# LM3670_3_3.net
KiCad netlist of a schematic drawn in EAGLE
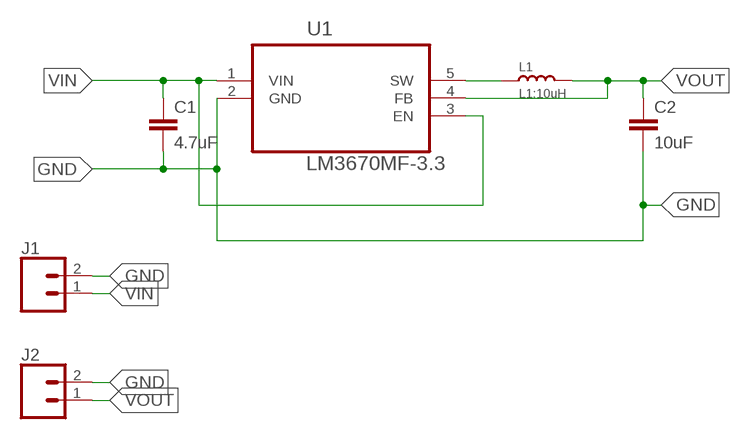
[diagram p0: schematic, sheet 1]

(export (version "E")
  (design (tool "Eeschema 10.0.6"))
  (components
    (comp (ref "C1")
      (value "4.7uF")
      (footprint "eagle-import:0603")
      (libsource (lib "eagle-import") (part "4.7UF0603"))
    )
    (comp (ref "C2")
      (value "10uF")
      (footprint "eagle-import:0805")
      (libsource (lib "eagle-import") (part "10UF-0805-10V-10%"))
    )
    (comp (ref "J1")
      (value "CONN_02")
      (footprint "eagle-import:1X02")
      (libsource (lib "eagle-import") (part "CONN_02"))
    )
    (comp (ref "J2")
      (value "CONN_02")
      (footprint "eagle-import:1X02")
      (libsource (lib "eagle-import") (part "CONN_02"))
    )
    (comp (ref "L1")
      (value "L1:10uH")
      (footprint "eagle-import:L0603")
      (fields (field (name "MPN") "BLM18AG121SN1D"))
      (libsource (lib "eagle-import") (part "SMD-FERRITE-CHIP-120-OHM-500MA(0603)"))
    )
    (comp (ref "U1")
      (value "LM3670MF-3.3")
      (footprint "eagle-import:SOT95P284X122-5N")
      (fields (field (name "MF") "Texas Instruments"))
      (libsource (lib "eagle-import") (part "LM3670MF-3.3"))
    )
  )
  (nets
    (net (code "1") (name "GND") (class "Default")
      (node (ref "C1") (pin "2") (pinfunction "2_2") (pintype "passive"))
      (node (ref "C2") (pin "2") (pinfunction "2_2") (pintype "passive"))
      (node (ref "J1") (pin "2") (pinfunction "2_2") (pintype "passive"))
      (node (ref "J2") (pin "2") (pinfunction "2_2") (pintype "passive"))
      (node (ref "U1") (pin "2") (pinfunction "GND_2") (pintype "passive"))
    )
    (net (code "2") (name "Net-(U1-SW)") (class "Default")
      (node (ref "L1") (pin "1") (pinfunction "1_1") (pintype "passive"))
      (node (ref "U1") (pin "5") (pinfunction "SW_5") (pintype "output"))
    )
    (net (code "3") (name "VIN") (class "Default")
      (node (ref "C1") (pin "1") (pinfunction "1_1") (pintype "passive"))
      (node (ref "J1") (pin "1") (pinfunction "1_1") (pintype "passive"))
      (node (ref "U1") (pin "1") (pinfunction "VIN_1") (pintype "input"))
      (node (ref "U1") (pin "3") (pinfunction "EN_3") (pintype "passive"))
    )
    (net (code "4") (name "VOUT") (class "Default")
      (node (ref "C2") (pin "1") (pinfunction "1_1") (pintype "passive"))
      (node (ref "J2") (pin "1") (pinfunction "1_1") (pintype "passive"))
      (node (ref "L1") (pin "2") (pinfunction "2_2") (pintype "passive"))
      (node (ref "U1") (pin "4") (pinfunction "FB_4") (pintype "passive"))
    )
  )
)
